# v1.net
KiCad netlist of a schematic drawn in EAGLE
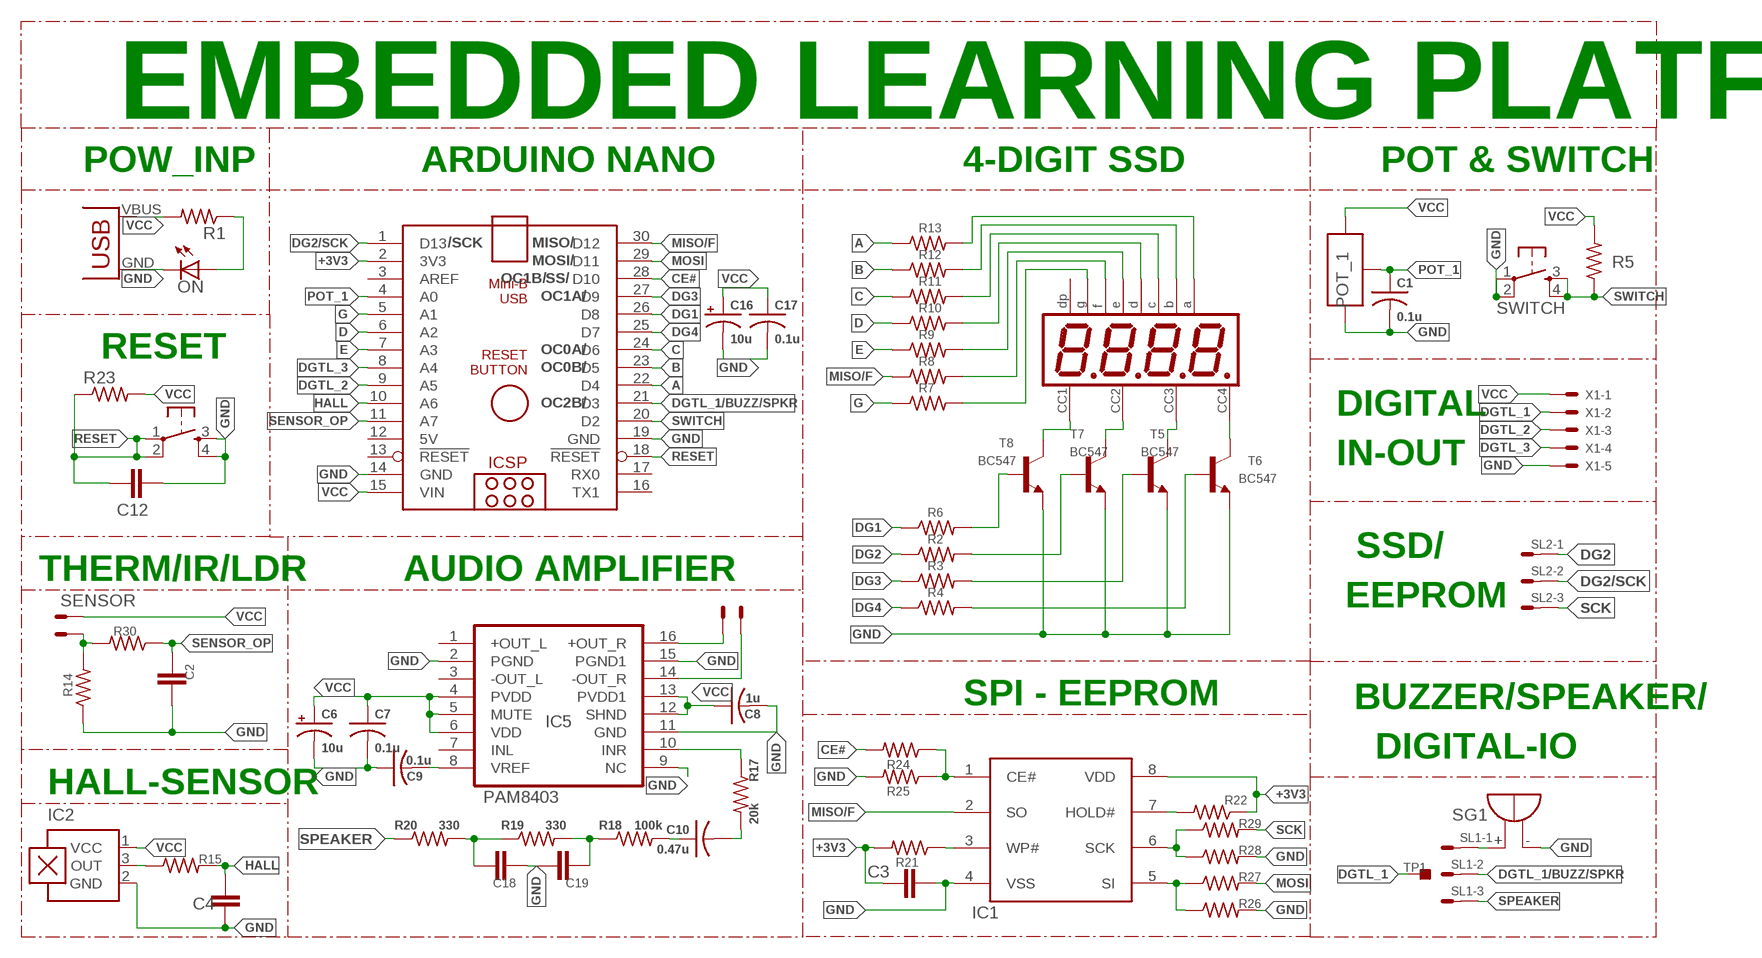
[diagram p0: schematic, sheet 1]

(export (version "E")
  (design (tool "Eeschema 10.0.6"))
  (components
    (comp (ref "ARDUINO_NANO1")
      (value "ARDUINO_NANO")
      (footprint "eagle-import:ARDUINO_NANO")
      (libsource (lib "eagle-import") (part "ARDUINO_NANO"))
    )
    (comp (ref "C1")
      (value "0.1u")
      (footprint "eagle-import:C0603")
      (libsource (lib "eagle-import") (part "CAP0603"))
    )
    (comp (ref "C2")
      (value "0.1u")
      (footprint "eagle-import:C0805")
      (libsource (lib "eagle-import") (part "C-EUC0805"))
    )
    (comp (ref "C3")
      (value "0.1u")
      (footprint "eagle-import:C0805")
      (libsource (lib "eagle-import") (part "rcl_C-EUC0805"))
    )
    (comp (ref "C4")
      (value "0.1u")
      (footprint "eagle-import:C0805")
      (libsource (lib "eagle-import") (part "rcl_C-EUC0805"))
    )
    (comp (ref "C6")
      (value "10u")
      (footprint "eagle-import:B_3528-21R")
      (libsource (lib "eagle-import") (part "CAP_POL_16V"))
    )
    (comp (ref "C7")
      (value "0.1u")
      (footprint "eagle-import:C0603")
      (libsource (lib "eagle-import") (part "CAP0603"))
    )
    (comp (ref "C8")
      (value "1u")
      (footprint "eagle-import:C0603")
      (libsource (lib "eagle-import") (part "CAP0603"))
    )
    (comp (ref "C9")
      (value "0.1u")
      (footprint "eagle-import:C0603")
      (libsource (lib "eagle-import") (part "CAP0603"))
    )
    (comp (ref "C10")
      (value "0.47u")
      (footprint "eagle-import:C0603")
      (libsource (lib "eagle-import") (part "CAP0603"))
    )
    (comp (ref "C12")
      (value "0.1u")
      (footprint "eagle-import:C0805")
      (libsource (lib "eagle-import") (part "rcl_C-EUC0805"))
    )
    (comp (ref "C16")
      (value "10u")
      (footprint "eagle-import:B_3528-21R")
      (libsource (lib "eagle-import") (part "CAP_POL_16V"))
    )
    (comp (ref "C17")
      (value "0.1u")
      (footprint "eagle-import:C0603")
      (libsource (lib "eagle-import") (part "CAP0603"))
    )
    (comp (ref "C18")
      (value "0.1u")
      (footprint "eagle-import:C0805")
      (libsource (lib "eagle-import") (part "C-EUC0805"))
    )
    (comp (ref "C19")
      (value "0.1uf")
      (footprint "eagle-import:C0805")
      (libsource (lib "eagle-import") (part "C-EUC0805"))
    )
    (comp (ref "DIS1")
      (value "NFD-5641AS-ALT")
      (footprint "eagle-import:NFD-5641")
      (libsource (lib "eagle-import") (part "NFD-5641AS-ALT"))
    )
    (comp (ref "IC1")
      (value "SST25VF040B_SPI_FLASH")
      (footprint "eagle-import:SOIC08")
      (libsource (lib "eagle-import") (part "SST25VF040B_SPI_FLASH"))
    )
    (comp (ref "IC2")
      (value "HALL SENSOR")
      (footprint "eagle-import:SIP3-UA")
      (fields (field (name "MF") "ALLEGRO MICROSYSTEMS, INC.") (field (name "MPN") "A1301EUA-T"))
      (libsource (lib "eagle-import") (part "A13?UA01"))
    )
    (comp (ref "IC5")
      (value "PAM8403")
      (footprint "eagle-import:SOP-16")
      (libsource (lib "eagle-import") (part "PAM8403"))
    )
    (comp (ref "ON")
      (value "LED3MM")
      (footprint "eagle-import:LED3MM")
      (libsource (lib "eagle-import") (part "LED3MM"))
    )
    (comp (ref "POT_1")
      (value "POTNORMAL")
      (footprint "eagle-import:RJ9W")
      (libsource (lib "eagle-import") (part "POTNORMAL"))
    )
    (comp (ref "R1")
      (value "R-US_0204/7")
      (footprint "eagle-import:0204_7")
      (libsource (lib "eagle-import") (part "R-US_0204/7"))
    )
    (comp (ref "R2")
      (value "R-US_0204/7")
      (footprint "eagle-import:0204_7")
      (libsource (lib "eagle-import") (part "R-US_0204/7"))
    )
    (comp (ref "R3")
      (value "R-US_0204/7")
      (footprint "eagle-import:0204_7")
      (libsource (lib "eagle-import") (part "R-US_0204/7"))
    )
    (comp (ref "R4")
      (value "R-US_0204/7")
      (footprint "eagle-import:0204_7")
      (libsource (lib "eagle-import") (part "R-US_0204/7"))
    )
    (comp (ref "R5")
      (value "R-US_0204/7")
      (footprint "eagle-import:0204_7")
      (libsource (lib "eagle-import") (part "R-US_0204/7"))
    )
    (comp (ref "R6")
      (value "R-US_0204/7")
      (footprint "eagle-import:0204_7")
      (libsource (lib "eagle-import") (part "R-US_0204/7"))
    )
    (comp (ref "R7")
      (value "R-US_0204/7")
      (footprint "eagle-import:0204_7")
      (libsource (lib "eagle-import") (part "R-US_0204/7"))
    )
    (comp (ref "R8")
      (value "R-US_0204/7")
      (footprint "eagle-import:0204_7")
      (libsource (lib "eagle-import") (part "R-US_0204/7"))
    )
    (comp (ref "R9")
      (value "R-US_0204/7")
      (footprint "eagle-import:0204_7")
      (libsource (lib "eagle-import") (part "R-US_0204/7"))
    )
    (comp (ref "R10")
      (value "R-US_0204/7")
      (footprint "eagle-import:0204_7")
      (libsource (lib "eagle-import") (part "R-US_0204/7"))
    )
    (comp (ref "R11")
      (value "R-US_0204/7")
      (footprint "eagle-import:0204_7")
      (libsource (lib "eagle-import") (part "R-US_0204/7"))
    )
    (comp (ref "R12")
      (value "R-US_0204/7")
      (footprint "eagle-import:0204_7")
      (libsource (lib "eagle-import") (part "R-US_0204/7"))
    )
    (comp (ref "R13")
      (value "R-US_0204/7")
      (footprint "eagle-import:0204_7")
      (libsource (lib "eagle-import") (part "R-US_0204/7"))
    )
    (comp (ref "R14")
      (value "R-US_0204/7")
      (footprint "eagle-import:0204_7")
      (libsource (lib "eagle-import") (part "R-US_0204/7"))
    )
    (comp (ref "R15")
      (value "R-US_0204/7")
      (footprint "eagle-import:0204_7")
      (libsource (lib "eagle-import") (part "R-US_0204/7"))
    )
    (comp (ref "R17")
      (value "20k")
      (footprint "eagle-import:M0805")
      (libsource (lib "eagle-import") (part "R-US_M0805"))
    )
    (comp (ref "R18")
      (value "100k")
      (footprint "eagle-import:M0805")
      (libsource (lib "eagle-import") (part "R-US_M0805"))
    )
    (comp (ref "R19")
      (value "330")
      (footprint "eagle-import:M0805")
      (libsource (lib "eagle-import") (part "R-US_M0805"))
    )
    (comp (ref "R20")
      (value "330")
      (footprint "eagle-import:M0805")
      (libsource (lib "eagle-import") (part "R-US_M0805"))
    )
    (comp (ref "R21")
      (value "R-US_0204/7")
      (footprint "eagle-import:0204_7")
      (libsource (lib "eagle-import") (part "R-US_0204/7"))
    )
    (comp (ref "R22")
      (value "R-US_0204/7")
      (footprint "eagle-import:0204_7")
      (libsource (lib "eagle-import") (part "R-US_0204/7"))
    )
    (comp (ref "R23")
      (value "R-US_0204/7")
      (footprint "eagle-import:0204_7")
      (libsource (lib "eagle-import") (part "resistor_348_R-US_0204/7"))
    )
    (comp (ref "R24")
      (value "R-US_0204/7")
      (footprint "eagle-import:0204_7")
      (libsource (lib "eagle-import") (part "R-US_0204/7"))
    )
    (comp (ref "R25")
      (value "R-US_0204/7")
      (footprint "eagle-import:0204_7")
      (libsource (lib "eagle-import") (part "R-US_0204/7"))
    )
    (comp (ref "R26")
      (value "R-US_0204/7")
      (footprint "eagle-import:0204_7")
      (libsource (lib "eagle-import") (part "R-US_0204/7"))
    )
    (comp (ref "R27")
      (value "R-US_0204/7")
      (footprint "eagle-import:0204_7")
      (libsource (lib "eagle-import") (part "R-US_0204/7"))
    )
    (comp (ref "R28")
      (value "R-US_0204/7")
      (footprint "eagle-import:0204_7")
      (libsource (lib "eagle-import") (part "R-US_0204/7"))
    )
    (comp (ref "R29")
      (value "R-US_0204/7")
      (footprint "eagle-import:0204_7")
      (libsource (lib "eagle-import") (part "R-US_0204/7"))
    )
    (comp (ref "R30")
      (value "R-US_0204/7")
      (footprint "eagle-import:0204_7")
      (libsource (lib "eagle-import") (part "R-US_0204/7"))
    )
    (comp (ref "RESET")
      (value "10xx")
      (footprint "eagle-import:B3F-10XX")
      (libsource (lib "eagle-import") (part "OMRON_SWITCH_10-XX"))
    )
    (comp (ref "SG1")
      (value "BUZZER")
      (footprint "eagle-import:F_TMB")
      (libsource (lib "eagle-import") (part "BUZZER"))
    )
    (comp (ref "SL1")
      (value "M03S")
      (footprint "eagle-import:03P")
      (libsource (lib "eagle-import") (part "M03S"))
    )
    (comp (ref "SL2")
      (value "M03S")
      (footprint "eagle-import:03P")
      (libsource (lib "eagle-import") (part "M03S"))
    )
    (comp (ref "SPEAKER")
      (value "SPEAKER")
      (footprint "eagle-import:JST-XH-02-PACKAGE-LONG-PAD")
      (libsource (lib "eagle-import") (part "JST-XH-02-PIN-LONG-PAD"))
    )
    (comp (ref "SWITCH")
      (value "OMRON_SWITCH_40-XX")
      (footprint "eagle-import:B3F-40XX")
      (libsource (lib "eagle-import") (part "OMRON_SWITCH_40-XX"))
    )
    (comp (ref "T5")
      (value "BC547")
      (footprint "eagle-import:TO92")
      (libsource (lib "eagle-import") (part "BC547"))
    )
    (comp (ref "T6")
      (value "BC547")
      (footprint "eagle-import:TO92")
      (libsource (lib "eagle-import") (part "BC547"))
    )
    (comp (ref "T7")
      (value "BC547")
      (footprint "eagle-import:TO92")
      (libsource (lib "eagle-import") (part "BC547"))
    )
    (comp (ref "T8")
      (value "BC547")
      (footprint "eagle-import:TO92")
      (libsource (lib "eagle-import") (part "BC547"))
    )
    (comp (ref "TP1")
      (value "TESTPOINT_TPS-PAD-036")
      (footprint "eagle-import:TESTPOINT_PAD-036")
      (libsource (lib "eagle-import") (part "TESTPOINT_TPS-PAD-036"))
    )
    (comp (ref "U$2")
      (value "USB(POWER)")
      (footprint "eagle-import:USB(POWER)")
      (libsource (lib "eagle-import") (part "USB(POWER)"))
    )
    (comp (ref "X1")
      (value "JST-XH-05-PIN-LONG-PAD")
      (footprint "eagle-import:JST-XH-05-PACKAGE-LONG-PAD")
      (libsource (lib "eagle-import") (part "JST-XH-05-PIN-LONG-PAD"))
    )
    (comp (ref "X2")
      (value "SENSOR")
      (footprint "eagle-import:JST-XH-02-PACKAGE-LONG-PAD")
      (libsource (lib "eagle-import") (part "JST-XH-02-PIN-LONG-PAD"))
    )
  )
  (nets
    (net (code "1") (name "+3V3") (class "Default")
      (node (ref "ARDUINO_NANO1") (pin "2") (pinfunction "3V3_2") (pintype "output"))
      (node (ref "C3") (pin "1") (pinfunction "1_1") (pintype "passive"))
      (node (ref "IC1") (pin "8") (pinfunction "VDD_8") (pintype "passive"))
      (node (ref "R21") (pin "2") (pinfunction "2_2") (pintype "passive"))
      (node (ref "R22") (pin "1") (pinfunction "1_1") (pintype "passive"))
    )
    (net (code "2") (name "/5V") (class "Default")
      (node (ref "ARDUINO_NANO1") (pin "12") (pinfunction "5V_12") (pintype "power_in"))
    )
    (net (code "3") (name "A") (class "Default")
      (node (ref "ARDUINO_NANO1") (pin "22") (pinfunction "D4_22") (pintype "bidirectional"))
      (node (ref "R13") (pin "1") (pinfunction "1_1") (pintype "passive"))
    )
    (net (code "4") (name "B") (class "Default")
      (node (ref "ARDUINO_NANO1") (pin "23") (pinfunction "D5_23") (pintype "bidirectional"))
      (node (ref "R12") (pin "1") (pinfunction "1_1") (pintype "passive"))
    )
    (net (code "5") (name "C") (class "Default")
      (node (ref "ARDUINO_NANO1") (pin "24") (pinfunction "D6_24") (pintype "bidirectional"))
      (node (ref "R11") (pin "1") (pinfunction "1_1") (pintype "passive"))
    )
    (net (code "6") (name "CE#") (class "Default")
      (node (ref "ARDUINO_NANO1") (pin "28") (pinfunction "D10_28") (pintype "bidirectional"))
      (node (ref "R24") (pin "2") (pinfunction "2_2") (pintype "passive"))
    )
    (net (code "7") (name "D") (class "Default")
      (node (ref "ARDUINO_NANO1") (pin "6") (pinfunction "A2_6") (pintype "bidirectional"))
      (node (ref "R10") (pin "1") (pinfunction "1_1") (pintype "passive"))
    )
    (net (code "8") (name "DG1") (class "Default")
      (node (ref "ARDUINO_NANO1") (pin "26") (pinfunction "D8_26") (pintype "bidirectional"))
      (node (ref "R6") (pin "1") (pinfunction "1_1") (pintype "passive"))
    )
    (net (code "9") (name "DG2") (class "Default")
      (node (ref "R2") (pin "1") (pinfunction "1_1") (pintype "passive"))
      (node (ref "SL2") (pin "1") (pinfunction "S_1") (pintype "passive"))
    )
    (net (code "10") (name "DG2{slash}SCK") (class "Default")
      (node (ref "ARDUINO_NANO1") (pin "1") (pinfunction "D13_1") (pintype "bidirectional"))
      (node (ref "SL2") (pin "2") (pinfunction "S_2") (pintype "passive"))
    )
    (net (code "11") (name "DG3") (class "Default")
      (node (ref "ARDUINO_NANO1") (pin "27") (pinfunction "D9_27") (pintype "bidirectional"))
      (node (ref "R3") (pin "1") (pinfunction "1_1") (pintype "passive"))
    )
    (net (code "12") (name "DG4") (class "Default")
      (node (ref "ARDUINO_NANO1") (pin "25") (pinfunction "D7_25") (pintype "bidirectional"))
      (node (ref "R4") (pin "1") (pinfunction "1_1") (pintype "passive"))
    )
    (net (code "13") (name "DGTL_1") (class "Default")
      (node (ref "TP1") (pin "1") (pinfunction "TP_1") (pintype "passive"))
      (node (ref "X1") (pin "2") (pinfunction "S_2") (pintype "passive"))
    )
    (net (code "14") (name "DGTL_1{slash}BUZZ{slash}SPKR") (class "Default")
      (node (ref "ARDUINO_NANO1") (pin "21") (pinfunction "D3_21") (pintype "bidirectional"))
      (node (ref "SL1") (pin "2") (pinfunction "S_2") (pintype "passive"))
    )
    (net (code "15") (name "DGTL_2") (class "Default")
      (node (ref "ARDUINO_NANO1") (pin "9") (pinfunction "A5_9") (pintype "bidirectional"))
      (node (ref "X1") (pin "3") (pinfunction "S_3") (pintype "passive"))
    )
    (net (code "16") (name "DGTL_3") (class "Default")
      (node (ref "ARDUINO_NANO1") (pin "8") (pinfunction "A4_8") (pintype "bidirectional"))
      (node (ref "X1") (pin "4") (pinfunction "S_4") (pintype "passive"))
    )
    (net (code "17") (name "E") (class "Default")
      (node (ref "ARDUINO_NANO1") (pin "7") (pinfunction "A3_7") (pintype "bidirectional"))
      (node (ref "R9") (pin "1") (pinfunction "1_1") (pintype "passive"))
    )
    (net (code "18") (name "G") (class "Default")
      (node (ref "ARDUINO_NANO1") (pin "5") (pinfunction "A1_5") (pintype "bidirectional"))
      (node (ref "R7") (pin "1") (pinfunction "1_1") (pintype "passive"))
    )
    (net (code "19") (name "GND") (class "Default")
      (node (ref "ARDUINO_NANO1") (pin "14") (pinfunction "GND_14") (pintype "power_in"))
      (node (ref "ARDUINO_NANO1") (pin "19") (pinfunction "GND_19") (pintype "power_in"))
      (node (ref "C1") (pin "2") (pinfunction "2_2") (pintype "passive"))
      (node (ref "C12") (pin "2") (pinfunction "2_2") (pintype "passive"))
      (node (ref "C16") (pin "-") (pinfunction "-_-") (pintype "passive"))
      (node (ref "C17") (pin "2") (pinfunction "2_2") (pintype "passive"))
      (node (ref "C18") (pin "2") (pinfunction "2_2") (pintype "passive"))
      (node (ref "C19") (pin "2") (pinfunction "2_2") (pintype "passive"))
      (node (ref "C2") (pin "1") (pinfunction "1_1") (pintype "passive"))
      (node (ref "C3") (pin "2") (pinfunction "2_2") (pintype "passive"))
      (node (ref "C4") (pin "1") (pinfunction "1_1") (pintype "passive"))
      (node (ref "C6") (pin "-") (pinfunction "-_-") (pintype "passive"))
      (node (ref "C7") (pin "2") (pinfunction "2_2") (pintype "passive"))
      (node (ref "C8") (pin "2") (pinfunction "2_2") (pintype "passive"))
      (node (ref "C9") (pin "1") (pinfunction "1_1") (pintype "passive"))
      (node (ref "IC1") (pin "4") (pinfunction "VSS_4") (pintype "passive"))
      (node (ref "IC2") (pin "2") (pinfunction "GND_2") (pintype "power_in"))
      (node (ref "IC5") (pin "11") (pinfunction "GND_11") (pintype "output"))
      (node (ref "IC5") (pin "15") (pinfunction "PGND1_15") (pintype "output"))
      (node (ref "IC5") (pin "2") (pinfunction "PGND_2") (pintype "input"))
      (node (ref "IC5") (pin "9") (pinfunction "NC_9") (pintype "output"))
      (node (ref "ON") (pin "K") (pinfunction "C_K") (pintype "passive"))
      (node (ref "POT_1") (pin "E") (pinfunction "E_E") (pintype "passive"))
      (node (ref "R14") (pin "1") (pinfunction "1_1") (pintype "passive"))
      (node (ref "R25") (pin "2") (pinfunction "2_2") (pintype "passive"))
      (node (ref "R26") (pin "2") (pinfunction "2_2") (pintype "passive"))
      (node (ref "R28") (pin "2") (pinfunction "2_2") (pintype "passive"))
      (node (ref "RESET") (pin "3") (pinfunction "S_3") (pintype "passive"))
      (node (ref "RESET") (pin "4") (pinfunction "S1_4") (pintype "passive"))
      (node (ref "SG1") (pin "-") (pinfunction "-_-") (pintype "passive"))
      (node (ref "SWITCH") (pin "1") (pinfunction "P_1") (pintype "passive"))
      (node (ref "SWITCH") (pin "2") (pinfunction "P1_2") (pintype "passive"))
      (node (ref "T5") (pin "1") (pinfunction "E_1") (pintype "passive"))
      (node (ref "T6") (pin "1") (pinfunction "E_1") (pintype "passive"))
      (node (ref "T7") (pin "1") (pinfunction "E_1") (pintype "passive"))
      (node (ref "T8") (pin "1") (pinfunction "E_1") (pintype "passive"))
      (node (ref "U$2") (pin "GND") (pinfunction "GND_GND") (pintype "power_in"))
      (node (ref "X1") (pin "5") (pinfunction "S_5") (pintype "passive"))
    )
    (net (code "20") (name "HALL") (class "Default")
      (node (ref "ARDUINO_NANO1") (pin "10") (pinfunction "A6_10") (pintype "bidirectional"))
      (node (ref "C4") (pin "2") (pinfunction "2_2") (pintype "passive"))
      (node (ref "R15") (pin "2") (pinfunction "2_2") (pintype "passive"))
    )
    (net (code "21") (name "MISO{slash}F") (class "Default")
      (node (ref "ARDUINO_NANO1") (pin "30") (pinfunction "D12_30") (pintype "bidirectional"))
      (node (ref "IC1") (pin "2") (pinfunction "SO_2") (pintype "passive"))
      (node (ref "R8") (pin "1") (pinfunction "1_1") (pintype "passive"))
    )
    (net (code "22") (name "MOSI") (class "Default")
      (node (ref "ARDUINO_NANO1") (pin "29") (pinfunction "D11_29") (pintype "bidirectional"))
      (node (ref "R27") (pin "2") (pinfunction "2_2") (pintype "passive"))
    )
    (net (code "23") (name "Net-(C10-Pad1)") (class "Default")
      (node (ref "C10") (pin "1") (pinfunction "1_1") (pintype "passive"))
      (node (ref "R18") (pin "2") (pinfunction "2_2") (pintype "passive"))
    )
    (net (code "24") (name "Net-(C10-Pad2)") (class "Default")
      (node (ref "C10") (pin "2") (pinfunction "2_2") (pintype "passive"))
      (node (ref "R17") (pin "2") (pinfunction "2_2") (pintype "passive"))
    )
    (net (code "25") (name "Net-(C18-Pad1)") (class "Default")
      (node (ref "C18") (pin "1") (pinfunction "1_1") (pintype "passive"))
      (node (ref "R19") (pin "1") (pinfunction "1_1") (pintype "passive"))
      (node (ref "R20") (pin "2") (pinfunction "2_2") (pintype "passive"))
    )
    (net (code "26") (name "Net-(C19-Pad1)") (class "Default")
      (node (ref "C19") (pin "1") (pinfunction "1_1") (pintype "passive"))
      (node (ref "R18") (pin "1") (pinfunction "1_1") (pintype "passive"))
      (node (ref "R19") (pin "2") (pinfunction "2_2") (pintype "passive"))
    )
    (net (code "27") (name "Net-(DIS1-PadP$1)") (class "Default")
      (node (ref "DIS1") (pin "P$1") (pinfunction "P$1_P$1") (pintype "bidirectional"))
      (node (ref "R9") (pin "2") (pinfunction "2_2") (pintype "passive"))
    )
    (net (code "28") (name "Net-(DIS1-PadP$2)") (class "Default")
      (node (ref "DIS1") (pin "P$2") (pinfunction "P$2_P$2") (pintype "bidirectional"))
      (node (ref "R10") (pin "2") (pinfunction "2_2") (pintype "passive"))
    )
    (net (code "29") (name "Net-(DIS1-PadP$4)") (class "Default")
      (node (ref "DIS1") (pin "P$4") (pinfunction "P$4_P$4") (pintype "bidirectional"))
      (node (ref "R11") (pin "2") (pinfunction "2_2") (pintype "passive"))
    )
    (net (code "30") (name "Net-(DIS1-PadP$5)") (class "Default")
      (node (ref "DIS1") (pin "P$5") (pinfunction "P$5_P$5") (pintype "bidirectional"))
      (node (ref "R7") (pin "2") (pinfunction "2_2") (pintype "passive"))
    )
    (net (code "31") (name "Net-(DIS1-PadP$7)") (class "Default")
      (node (ref "DIS1") (pin "P$7") (pinfunction "P$7_P$7") (pintype "bidirectional"))
      (node (ref "R12") (pin "2") (pinfunction "2_2") (pintype "passive"))
    )
    (net (code "32") (name "Net-(DIS1-PadP$10)") (class "Default")
      (node (ref "DIS1") (pin "P$10") (pinfunction "P$10_P$10") (pintype "bidirectional"))
      (node (ref "R8") (pin "2") (pinfunction "2_2") (pintype "passive"))
    )
    (net (code "33") (name "Net-(DIS1-PadP$11)") (class "Default")
      (node (ref "DIS1") (pin "P$11") (pinfunction "P$11_P$11") (pintype "bidirectional"))
      (node (ref "R13") (pin "2") (pinfunction "2_2") (pintype "passive"))
    )
    (net (code "34") (name "Net-(IC1-CE#)") (class "Default")
      (node (ref "IC1") (pin "1") (pinfunction "CE#_1") (pintype "passive"))
      (node (ref "R24") (pin "1") (pinfunction "1_1") (pintype "passive"))
      (node (ref "R25") (pin "1") (pinfunction "1_1") (pintype "passive"))
    )
    (net (code "35") (name "Net-(IC1-HOLD#)") (class "Default")
      (node (ref "IC1") (pin "7") (pinfunction "HOLD#_7") (pintype "passive"))
      (node (ref "R22") (pin "2") (pinfunction "2_2") (pintype "passive"))
    )
    (net (code "36") (name "Net-(IC1-SCK)") (class "Default")
      (node (ref "IC1") (pin "6") (pinfunction "SCK_6") (pintype "passive"))
      (node (ref "R28") (pin "1") (pinfunction "1_1") (pintype "passive"))
      (node (ref "R29") (pin "1") (pinfunction "1_1") (pintype "passive"))
    )
    (net (code "37") (name "Net-(IC1-SI)") (class "Default")
      (node (ref "IC1") (pin "5") (pinfunction "SI_5") (pintype "passive"))
      (node (ref "R26") (pin "1") (pinfunction "1_1") (pintype "passive"))
      (node (ref "R27") (pin "1") (pinfunction "1_1") (pintype "passive"))
    )
    (net (code "38") (name "Net-(IC1-WP#)") (class "Default")
      (node (ref "IC1") (pin "3") (pinfunction "WP#_3") (pintype "passive"))
      (node (ref "R21") (pin "1") (pinfunction "1_1") (pintype "passive"))
    )
    (net (code "39") (name "Net-(IC2-OUT)") (class "Default")
      (node (ref "IC2") (pin "3") (pinfunction "OUT_3") (pintype "output"))
      (node (ref "R15") (pin "1") (pinfunction "1_1") (pintype "passive"))
    )
    (net (code "40") (name "Net-(IC5-+OUT_R)") (class "Default")
      (node (ref "IC5") (pin "16") (pinfunction "+OUT_R_16") (pintype "output"))
      (node (ref "SPEAKER") (pin "1") (pinfunction "S_1") (pintype "passive"))
    )
    (net (code "41") (name "Net-(IC5--OUT_R)") (class "Default")
      (node (ref "IC5") (pin "14") (pinfunction "-OUT_R_14") (pintype "output"))
      (node (ref "SPEAKER") (pin "2") (pinfunction "S_2") (pintype "passive"))
    )
    (net (code "42") (name "Net-(IC5-INR)") (class "Default")
      (node (ref "IC5") (pin "10") (pinfunction "INR_10") (pintype "output"))
      (node (ref "R17") (pin "1") (pinfunction "1_1") (pintype "passive"))
    )
    (net (code "43") (name "Net-(IC5-VREF)") (class "Default")
      (node (ref "C9") (pin "2") (pinfunction "2_2") (pintype "passive"))
      (node (ref "IC5") (pin "8") (pinfunction "VREF_8") (pintype "input"))
    )
    (net (code "44") (name "Net-(ON-PadA)") (class "Default")
      (node (ref "ON") (pin "A") (pinfunction "A_A") (pintype "passive"))
      (node (ref "R1") (pin "1") (pinfunction "1_1") (pintype "passive"))
    )
    (net (code "45") (name "Net-(SL1A-S)") (class "Default")
      (node (ref "SG1") (pin "+") (pinfunction "+_+") (pintype "passive"))
      (node (ref "SL1") (pin "1") (pinfunction "S_1") (pintype "passive"))
    )
    (net (code "46") (name "Net-(T5-B)") (class "Default")
      (node (ref "R3") (pin "2") (pinfunction "2_2") (pintype "passive"))
      (node (ref "T5") (pin "2") (pinfunction "B_2") (pintype "passive"))
    )
    (net (code "47") (name "Net-(T5-C)") (class "Default")
      (node (ref "DIS1") (pin "P$8") (pinfunction "P$8_P$8") (pintype "bidirectional"))
      (node (ref "T5") (pin "3") (pinfunction "C_3") (pintype "passive"))
    )
    (net (code "48") (name "Net-(T6-B)") (class "Default")
      (node (ref "R4") (pin "2") (pinfunction "2_2") (pintype "passive"))
      (node (ref "T6") (pin "2") (pinfunction "B_2") (pintype "passive"))
    )
    (net (code "49") (name "Net-(T6-C)") (class "Default")
      (node (ref "DIS1") (pin "P$6") (pinfunction "P$6_P$6") (pintype "bidirectional"))
      (node (ref "T6") (pin "3") (pinfunction "C_3") (pintype "passive"))
    )
    (net (code "50") (name "Net-(T7-B)") (class "Default")
      (node (ref "R2") (pin "2") (pinfunction "2_2") (pintype "passive"))
      (node (ref "T7") (pin "2") (pinfunction "B_2") (pintype "passive"))
    )
    (net (code "51") (name "Net-(T7-C)") (class "Default")
      (node (ref "DIS1") (pin "P$9") (pinfunction "P$9_P$9") (pintype "bidirectional"))
      (node (ref "T7") (pin "3") (pinfunction "C_3") (pintype "passive"))
    )
    (net (code "52") (name "Net-(T8-B)") (class "Default")
      (node (ref "R6") (pin "2") (pinfunction "2_2") (pintype "passive"))
      (node (ref "T8") (pin "2") (pinfunction "B_2") (pintype "passive"))
    )
    (net (code "53") (name "Net-(T8-C)") (class "Default")
      (node (ref "DIS1") (pin "P$12") (pinfunction "P$12_P$12") (pintype "bidirectional"))
      (node (ref "T8") (pin "3") (pinfunction "C_3") (pintype "passive"))
    )
    (net (code "54") (name "POT_1") (class "Default")
      (node (ref "ARDUINO_NANO1") (pin "4") (pinfunction "A0_4") (pintype "bidirectional"))
      (node (ref "C1") (pin "1") (pinfunction "1_1") (pintype "passive"))
      (node (ref "POT_1") (pin "S") (pinfunction "S_S") (pintype "passive"))
    )
    (net (code "55") (name "RESET") (class "Default")
      (node (ref "ARDUINO_NANO1") (pin "18") (pinfunction "~{RESET}_18") (pintype "input"))
      (node (ref "C12") (pin "1") (pinfunction "1_1") (pintype "passive"))
      (node (ref "R23") (pin "1") (pinfunction "1_1") (pintype "passive"))
      (node (ref "RESET") (pin "1") (pinfunction "P_1") (pintype "passive"))
      (node (ref "RESET") (pin "2") (pinfunction "P1_2") (pintype "passive"))
    )
    (net (code "56") (name "SCK") (class "Default")
      (node (ref "R29") (pin "2") (pinfunction "2_2") (pintype "passive"))
      (node (ref "SL2") (pin "3") (pinfunction "S_3") (pintype "passive"))
    )
    (net (code "57") (name "SENSOR_OP") (class "Default")
      (node (ref "ARDUINO_NANO1") (pin "11") (pinfunction "A7_11") (pintype "bidirectional"))
      (node (ref "C2") (pin "2") (pinfunction "2_2") (pintype "passive"))
      (node (ref "R14") (pin "2") (pinfunction "2_2") (pintype "passive"))
      (node (ref "R30") (pin "1") (pinfunction "1_1") (pintype "passive"))
      (node (ref "R30") (pin "2") (pinfunction "2_2") (pintype "passive"))
      (node (ref "X2") (pin "1") (pinfunction "S_1") (pintype "passive"))
    )
    (net (code "58") (name "SPEAKER") (class "Default")
      (node (ref "R20") (pin "1") (pinfunction "1_1") (pintype "passive"))
      (node (ref "SL1") (pin "3") (pinfunction "S_3") (pintype "passive"))
    )
    (net (code "59") (name "SWITCH") (class "Default")
      (node (ref "ARDUINO_NANO1") (pin "20") (pinfunction "D2_20") (pintype "bidirectional"))
      (node (ref "R5") (pin "1") (pinfunction "1_1") (pintype "passive"))
      (node (ref "SWITCH") (pin "3") (pinfunction "S_3") (pintype "passive"))
      (node (ref "SWITCH") (pin "4") (pinfunction "S1_4") (pintype "passive"))
    )
    (net (code "60") (name "VCC") (class "Default")
      (node (ref "ARDUINO_NANO1") (pin "15") (pinfunction "VIN_15") (pintype "power_in"))
      (node (ref "C16") (pin "+") (pinfunction "+_+") (pintype "passive"))
      (node (ref "C17") (pin "1") (pinfunction "1_1") (pintype "passive"))
      (node (ref "C6") (pin "+") (pinfunction "+_+") (pintype "passive"))
      (node (ref "C7") (pin "1") (pinfunction "1_1") (pintype "passive"))
      (node (ref "C8") (pin "1") (pinfunction "1_1") (pintype "passive"))
      (node (ref "IC2") (pin "1") (pinfunction "VCC_1") (pintype "power_in"))
      (node (ref "IC5") (pin "12") (pinfunction "SHND_12") (pintype "output"))
      (node (ref "IC5") (pin "13") (pinfunction "PVDD1_13") (pintype "output"))
      (node (ref "IC5") (pin "4") (pinfunction "PVDD_4") (pintype "input"))
      (node (ref "IC5") (pin "5") (pinfunction "MUTE_5") (pintype "input"))
      (node (ref "IC5") (pin "6") (pinfunction "VDD_6") (pintype "input"))
      (node (ref "POT_1") (pin "A") (pinfunction "A_A") (pintype "passive"))
      (node (ref "R1") (pin "2") (pinfunction "2_2") (pintype "passive"))
      (node (ref "R23") (pin "2") (pinfunction "2_2") (pintype "passive"))
      (node (ref "R5") (pin "2") (pinfunction "2_2") (pintype "passive"))
      (node (ref "U$2") (pin "VBUS") (pinfunction "VCC_VBUS") (pintype "power_in"))
      (node (ref "X1") (pin "1") (pinfunction "S_1") (pintype "passive"))
      (node (ref "X2") (pin "2") (pinfunction "S_2") (pintype "passive"))
    )
    (net (code "61") (name "unconnected-(ARDUINO_NANO1-AREF-Pad3)") (class "Default")
      (node (ref "ARDUINO_NANO1") (pin "3") (pinfunction "AREF_3") (pintype "input"))
    )
    (net (code "62") (name "unconnected-(ARDUINO_NANO1-RX0-Pad17)") (class "Default")
      (node (ref "ARDUINO_NANO1") (pin "17") (pinfunction "RX0_17") (pintype "bidirectional"))
    )
    (net (code "63") (name "unconnected-(ARDUINO_NANO1-TX1-Pad16)") (class "Default")
      (node (ref "ARDUINO_NANO1") (pin "16") (pinfunction "TX1_16") (pintype "bidirectional"))
    )
    (net (code "64") (name "unconnected-(ARDUINO_NANO1-~{RESET}-Pad13)") (class "Default")
      (node (ref "ARDUINO_NANO1") (pin "13") (pinfunction "~{RESET}_13") (pintype "input"))
    )
    (net (code "65") (name "unconnected-(DIS1-PadP$3)") (class "Default")
      (node (ref "DIS1") (pin "P$3") (pinfunction "P$3_P$3") (pintype "bidirectional"))
    )
    (net (code "66") (name "unconnected-(IC5-+OUT_L-Pad1)") (class "Default")
      (node (ref "IC5") (pin "1") (pinfunction "+OUT_L_1") (pintype "input"))
    )
    (net (code "67") (name "unconnected-(IC5--OUT_L-Pad3)") (class "Default")
      (node (ref "IC5") (pin "3") (pinfunction "-OUT_L_3") (pintype "input"))
    )
    (net (code "68") (name "unconnected-(IC5-INL-Pad7)") (class "Default")
      (node (ref "IC5") (pin "7") (pinfunction "INL_7") (pintype "input"))
    )
  )
)
